# as14120_adc.net
KiCad netlist of a schematic drawn in Altium Designer
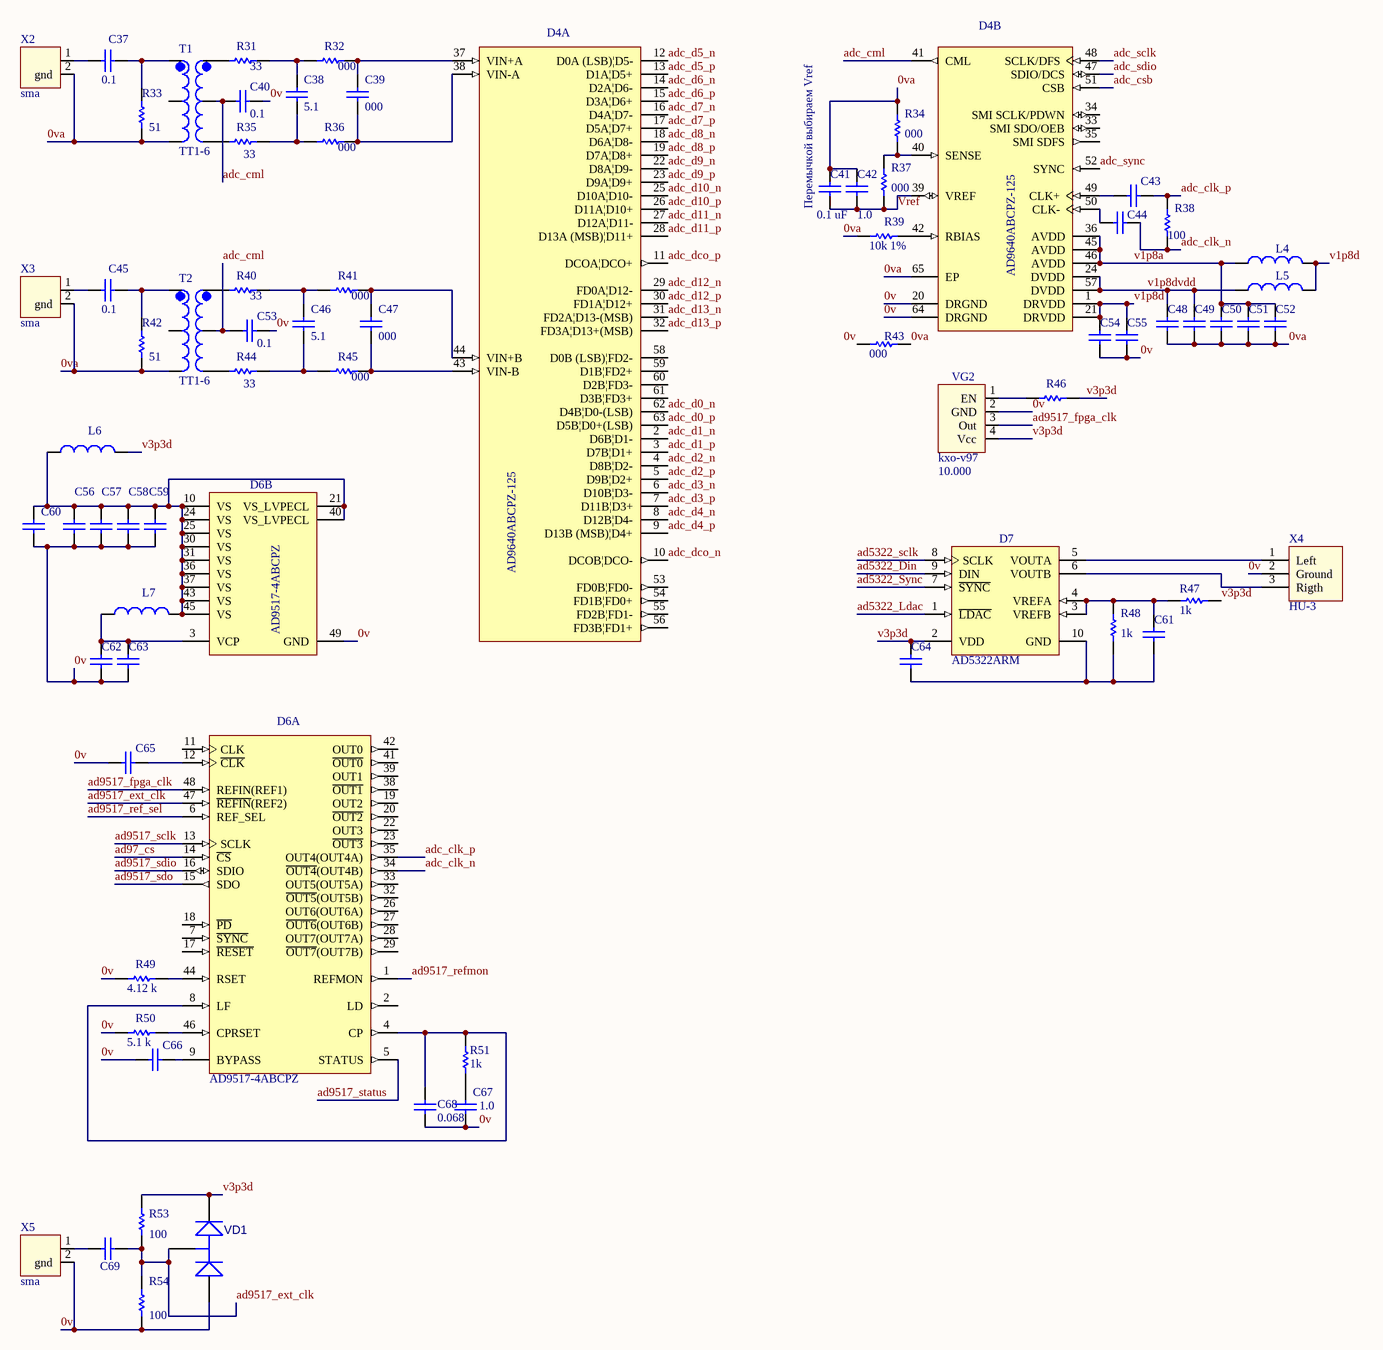
[diagram p0: as14120_adc.SchDoc]

(export (version "E")
  (design (tool "Eeschema 10.0.6"))
  (components
    (comp (ref "C37")
      (value "0.1")
      (footprint "CAPC0402(1005)60_M")
      (description "CAP 1uF 10V ±20% 0402 (1005 Metric) Thickness 0.6mm SMD")
      (fields (field (name "TOLERANCE") "±20%") (field (name "Comment") "CAP 1uF 10V 0402(1005)"))
      (libsource (lib "as14120") (part "CAP_0402"))
    )
    (comp (ref "C38")
      (value "5.1")
      (footprint "CAPC0805(2012)100_N")
      (fields (field (name "Comment") "CAP_0805"))
      (libsource (lib "as14120") (part "CAP_0805"))
    )
    (comp (ref "C39")
      (value "000")
      (footprint "CAPC0805(2012)100_N")
      (fields (field (name "Comment") "CAP_0805"))
      (libsource (lib "as14120") (part "CAP_0805"))
    )
    (comp (ref "C40")
      (value "0.1")
      (footprint "CAPC0402(1005)60_M")
      (description "CAP 1uF 10V ±20% 0402 (1005 Metric) Thickness 0.6mm SMD")
      (fields (field (name "TOLERANCE") "±20%") (field (name "Comment") "CAP 1uF 10V 0402(1005)"))
      (libsource (lib "as14120") (part "CAP_0402"))
    )
    (comp (ref "C41")
      (value "0.1 uF")
      (footprint "CAPC0402(1005)60_M")
      (description "CAP 1uF 10V ±20% 0402 (1005 Metric) Thickness 0.6mm SMD")
      (fields (field (name "TOLERANCE") "±20%") (field (name "Comment") "CAP 1uF 10V 0402(1005)"))
      (libsource (lib "as14120") (part "CAP_0402"))
    )
    (comp (ref "C42")
      (value "1.0")
      (footprint "CAPC0402(1005)60_M")
      (description "CAP 1uF 10V ±20% 0402 (1005 Metric) Thickness 0.6mm SMD")
      (fields (field (name "TOLERANCE") "±20%") (field (name "Comment") "CAP 1uF 10V 0402(1005)"))
      (libsource (lib "as14120") (part "CAP_0402"))
    )
    (comp (ref "C43")
      (value "CAP 1uF 10V 0402(1005)")
      (footprint "CAPC0402(1005)60_M")
      (description "CAP 1uF 10V ±20% 0402 (1005 Metric) Thickness 0.6mm SMD")
      (fields (field (name "TOLERANCE") "±20%"))
      (libsource (lib "as14120") (part "CAP_0402"))
    )
    (comp (ref "C44")
      (value "CAP 1uF 10V 0402(1005)")
      (footprint "CAPC0402(1005)60_M")
      (description "CAP 1uF 10V ±20% 0402 (1005 Metric) Thickness 0.6mm SMD")
      (fields (field (name "TOLERANCE") "±20%"))
      (libsource (lib "as14120") (part "CAP_0402"))
    )
    (comp (ref "C45")
      (value "0.1")
      (footprint "CAPC0402(1005)60_M")
      (description "CAP 1uF 10V ±20% 0402 (1005 Metric) Thickness 0.6mm SMD")
      (fields (field (name "TOLERANCE") "±20%") (field (name "Comment") "CAP 1uF 10V 0402(1005)"))
      (libsource (lib "as14120") (part "CAP_0402"))
    )
    (comp (ref "C46")
      (value "5.1")
      (footprint "CAPC0805(2012)100_N")
      (fields (field (name "Comment") "CAP_0805"))
      (libsource (lib "as14120") (part "CAP_0805"))
    )
    (comp (ref "C47")
      (value "000")
      (footprint "CAPC0805(2012)100_N")
      (fields (field (name "Comment") "CAP_0805"))
      (libsource (lib "as14120") (part "CAP_0805"))
    )
    (comp (ref "C48")
      (value "CAP 1uF 10V 0402(1005)")
      (footprint "CAPC0402(1005)60_M")
      (description "CAP 1uF 10V ±20% 0402 (1005 Metric) Thickness 0.6mm SMD")
      (fields (field (name "TOLERANCE") "±20%"))
      (libsource (lib "as14120") (part "CAP_0402"))
    )
    (comp (ref "C49")
      (value "CAP 1uF 10V 0402(1005)")
      (footprint "CAPC0402(1005)60_M")
      (description "CAP 1uF 10V ±20% 0402 (1005 Metric) Thickness 0.6mm SMD")
      (fields (field (name "TOLERANCE") "±20%"))
      (libsource (lib "as14120") (part "CAP_0402"))
    )
    (comp (ref "C50")
      (value "CAP 1uF 10V 0402(1005)")
      (footprint "CAPC0402(1005)60_M")
      (description "CAP 1uF 10V ±20% 0402 (1005 Metric) Thickness 0.6mm SMD")
      (fields (field (name "TOLERANCE") "±20%"))
      (libsource (lib "as14120") (part "CAP_0402"))
    )
    (comp (ref "C51")
      (value "CAP 1uF 10V 0402(1005)")
      (footprint "CAPC0402(1005)60_M")
      (description "CAP 1uF 10V ±20% 0402 (1005 Metric) Thickness 0.6mm SMD")
      (fields (field (name "TOLERANCE") "±20%"))
      (libsource (lib "as14120") (part "CAP_0402"))
    )
    (comp (ref "C52")
      (value "CAP 1uF 10V 0402(1005)")
      (footprint "CAPC0402(1005)60_M")
      (description "CAP 1uF 10V ±20% 0402 (1005 Metric) Thickness 0.6mm SMD")
      (fields (field (name "TOLERANCE") "±20%"))
      (libsource (lib "as14120") (part "CAP_0402"))
    )
    (comp (ref "C53")
      (value "0.1")
      (footprint "CAPC0402(1005)60_M")
      (description "CAP 1uF 10V ±20% 0402 (1005 Metric) Thickness 0.6mm SMD")
      (fields (field (name "TOLERANCE") "±20%") (field (name "Comment") "CAP 1uF 10V 0402(1005)"))
      (libsource (lib "as14120") (part "CAP_0402"))
    )
    (comp (ref "C54")
      (value "CAP 1uF 10V 0402(1005)")
      (footprint "CAPC0402(1005)60_M")
      (description "CAP 1uF 10V ±20% 0402 (1005 Metric) Thickness 0.6mm SMD")
      (fields (field (name "TOLERANCE") "±20%"))
      (libsource (lib "as14120") (part "CAP_0402"))
    )
    (comp (ref "C55")
      (value "CAP 1uF 10V 0402(1005)")
      (footprint "CAPC0402(1005)60_M")
      (description "CAP 1uF 10V ±20% 0402 (1005 Metric) Thickness 0.6mm SMD")
      (fields (field (name "TOLERANCE") "±20%"))
      (libsource (lib "as14120") (part "CAP_0402"))
    )
    (comp (ref "C56")
      (value "CAP 1uF 10V 0402(1005)")
      (footprint "CAPC0402(1005)60_M")
      (description "CAP 1uF 10V ±20% 0402 (1005 Metric) Thickness 0.6mm SMD")
      (fields (field (name "TOLERANCE") "±20%"))
      (libsource (lib "as14120") (part "CAP_0402"))
    )
    (comp (ref "C57")
      (value "CAP 1uF 10V 0402(1005)")
      (footprint "CAPC0402(1005)60_M")
      (description "CAP 1uF 10V ±20% 0402 (1005 Metric) Thickness 0.6mm SMD")
      (fields (field (name "TOLERANCE") "±20%"))
      (libsource (lib "as14120") (part "CAP_0402"))
    )
    (comp (ref "C58")
      (value "CAP 1uF 10V 0402(1005)")
      (footprint "CAPC0402(1005)60_M")
      (description "CAP 1uF 10V ±20% 0402 (1005 Metric) Thickness 0.6mm SMD")
      (fields (field (name "TOLERANCE") "±20%"))
      (libsource (lib "as14120") (part "CAP_0402"))
    )
    (comp (ref "C59")
      (value "CAP 1uF 10V 0402(1005)")
      (footprint "CAPC0402(1005)60_M")
      (description "CAP 1uF 10V ±20% 0402 (1005 Metric) Thickness 0.6mm SMD")
      (fields (field (name "TOLERANCE") "±20%"))
      (libsource (lib "as14120") (part "CAP_0402"))
    )
    (comp (ref "C60")
      (value "CAP 1uF 10V 0402(1005)")
      (footprint "CAPC0402(1005)60_M")
      (description "CAP 1uF 10V ±20% 0402 (1005 Metric) Thickness 0.6mm SMD")
      (fields (field (name "TOLERANCE") "±20%"))
      (libsource (lib "as14120") (part "CAP_0402"))
    )
    (comp (ref "C61")
      (value "CAP 1uF 10V 0402(1005)")
      (footprint "CAPC0402(1005)60_M")
      (description "CAP 1uF 10V ±20% 0402 (1005 Metric) Thickness 0.6mm SMD")
      (fields (field (name "TOLERANCE") "±20%"))
      (libsource (lib "as14120") (part "CAP_0402"))
    )
    (comp (ref "C62")
      (value "CAP 1uF 10V 0402(1005)")
      (footprint "CAPC0402(1005)60_M")
      (description "CAP 1uF 10V ±20% 0402 (1005 Metric) Thickness 0.6mm SMD")
      (fields (field (name "TOLERANCE") "±20%"))
      (libsource (lib "as14120") (part "CAP_0402"))
    )
    (comp (ref "C63")
      (value "CAP 1uF 10V 0402(1005)")
      (footprint "CAPC0402(1005)60_M")
      (description "CAP 1uF 10V ±20% 0402 (1005 Metric) Thickness 0.6mm SMD")
      (fields (field (name "TOLERANCE") "±20%"))
      (libsource (lib "as14120") (part "CAP_0402"))
    )
    (comp (ref "C64")
      (value "CAP 1uF 10V 0402(1005)")
      (footprint "CAPC0402(1005)60_M")
      (description "CAP 1uF 10V ±20% 0402 (1005 Metric) Thickness 0.6mm SMD")
      (fields (field (name "TOLERANCE") "±20%"))
      (libsource (lib "as14120") (part "CAP_0402"))
    )
    (comp (ref "C65")
      (value "CAP 1uF 10V 0402(1005)")
      (footprint "CAPC0402(1005)60_M")
      (description "CAP 1uF 10V ±20% 0402 (1005 Metric) Thickness 0.6mm SMD")
      (fields (field (name "TOLERANCE") "±20%"))
      (libsource (lib "as14120") (part "CAP_0402"))
    )
    (comp (ref "C66")
      (value "CAP 1uF 10V 0402(1005)")
      (footprint "CAPC0402(1005)60_M")
      (description "CAP 1uF 10V ±20% 0402 (1005 Metric) Thickness 0.6mm SMD")
      (fields (field (name "TOLERANCE") "±20%"))
      (libsource (lib "as14120") (part "CAP_0402"))
    )
    (comp (ref "C67")
      (value "1.0")
      (footprint "CAPC0805(2012)100_N")
      (fields (field (name "Comment") "CAP_0805"))
      (libsource (lib "as14120") (part "CAP_0805"))
    )
    (comp (ref "C68")
      (value "0.068")
      (footprint "CAPC0805(2012)100_N")
      (fields (field (name "Comment") "CAP_0805"))
      (libsource (lib "as14120") (part "CAP_0805"))
    )
    (comp (ref "C69")
      (value "CAP 1uF 10V 0402(1005)")
      (footprint "CAPC0402(1005)60_M")
      (description "CAP 1uF 10V ±20% 0402 (1005 Metric) Thickness 0.6mm SMD")
      (fields (field (name "TOLERANCE") "±20%"))
      (libsource (lib "as14120") (part "CAP_0402"))
    )
    (comp (ref "D4")
      (value "AD9640ABCPZ-125")
      (footprint "CP-64-6_N")
      (fields (field (name "PART NUMBER") "AD9640-125") (field (name "MANUFACTURER") "Analog Devices"))
      (libsource (lib "Analog Devices Data Converters Analog-to-Digital Converters") (part "AD9640ABCPZ-125"))
    )
    (comp (ref "D6")
      (value "AD9517-4ABCPZ")
      (footprint "ADI-CP-48-8_N")
      (libsource (lib "Analog Devices RF IF Timing ICs and Clocks") (part "AD9517-4ABCPZ"))
    )
    (comp (ref "D7")
      (value "AD5322ARM")
      (footprint "RM-10_L")
      (fields (field (name "ADI PART NUMBER") "AD5322") (field (name "MANUFACTURER") "Analog Devices"))
      (libsource (lib "Analog Devices Data Converters Digital-to-Analog Converters") (part "AD5322ARM"))
    )
    (comp (ref "L4")
      (value "BLM21PG300SN1D")
      (footprint "CAPC0805(2012)100_N")
      (libsource (lib "as14120") (part "Ferrite_beat"))
    )
    (comp (ref "L5")
      (value "BLM21PG300SN1D")
      (footprint "CAPC0805(2012)100_N")
      (libsource (lib "as14120") (part "Ferrite_beat"))
    )
    (comp (ref "L6")
      (value "BLM21PG300SN1D")
      (footprint "CAPC0805(2012)100_N")
      (libsource (lib "as14120") (part "Ferrite_beat"))
    )
    (comp (ref "L7")
      (value "BLM21PG300SN1D")
      (footprint "CAPC0805(2012)100_N")
      (libsource (lib "as14120") (part "Ferrite_beat"))
    )
    (comp (ref "R31")
      (value "33")
      (footprint "RESC0805(2012)_L")
      (description "1K 0.125W 1% 0805 (2012 Metric)  SMD")
      (fields (field (name "TOLERANCE") "1 %") (field (name "POWER") "0.125 W"))
      (libsource (lib "as14120") (part "RES_0805"))
    )
    (comp (ref "R32")
      (value "000")
      (footprint "RESC0805(2012)_L")
      (description "1K 0.125W 1% 0805 (2012 Metric)  SMD")
      (fields (field (name "TOLERANCE") "1 %") (field (name "POWER") "0.125 W"))
      (libsource (lib "as14120") (part "RES_0805"))
    )
    (comp (ref "R33")
      (value "51")
      (footprint "RESC0805(2012)_L")
      (description "1K 0.125W 1% 0805 (2012 Metric)  SMD")
      (fields (field (name "TOLERANCE") "1 %") (field (name "POWER") "0.125 W"))
      (libsource (lib "as14120") (part "RES_0805"))
    )
    (comp (ref "R34")
      (value "000")
      (footprint "RESC0603(1608)_L")
      (description "1K 0.1W 5% 0603 (1608 Metric)  SMD")
      (fields (field (name "TOLERANCE") "5 %") (field (name "POWER") "0.1 W"))
      (libsource (lib "as14120") (part "RES_0603"))
    )
    (comp (ref "R35")
      (value "33")
      (footprint "RESC0805(2012)_L")
      (description "1K 0.125W 1% 0805 (2012 Metric)  SMD")
      (fields (field (name "TOLERANCE") "1 %") (field (name "POWER") "0.125 W"))
      (libsource (lib "as14120") (part "RES_0805"))
    )
    (comp (ref "R36")
      (value "000")
      (footprint "RESC0805(2012)_L")
      (description "1K 0.125W 1% 0805 (2012 Metric)  SMD")
      (fields (field (name "TOLERANCE") "1 %") (field (name "POWER") "0.125 W"))
      (libsource (lib "as14120") (part "RES_0805"))
    )
    (comp (ref "R37")
      (value "000")
      (footprint "RESC0603(1608)_L")
      (description "1K 0.1W 5% 0603 (1608 Metric)  SMD")
      (fields (field (name "TOLERANCE") "5 %") (field (name "POWER") "0.1 W"))
      (libsource (lib "as14120") (part "RES_0603"))
    )
    (comp (ref "R38")
      (value "100")
      (footprint "RESC0805(2012)_L")
      (description "1K 0.125W 1% 0805 (2012 Metric)  SMD")
      (fields (field (name "TOLERANCE") "1 %") (field (name "POWER") "0.125 W"))
      (libsource (lib "as14120") (part "RES_0805"))
    )
    (comp (ref "R39")
      (value "10k 1%")
      (footprint "RESC0805(2012)_L")
      (description "1K 0.125W 1% 0805 (2012 Metric)  SMD")
      (fields (field (name "TOLERANCE") "1 %") (field (name "POWER") "0.125 W"))
      (libsource (lib "as14120") (part "RES_0805"))
    )
    (comp (ref "R40")
      (value "33")
      (footprint "RESC0805(2012)_L")
      (description "1K 0.125W 1% 0805 (2012 Metric)  SMD")
      (fields (field (name "TOLERANCE") "1 %") (field (name "POWER") "0.125 W"))
      (libsource (lib "as14120") (part "RES_0805"))
    )
    (comp (ref "R41")
      (value "000")
      (footprint "RESC0805(2012)_L")
      (description "1K 0.125W 1% 0805 (2012 Metric)  SMD")
      (fields (field (name "TOLERANCE") "1 %") (field (name "POWER") "0.125 W"))
      (libsource (lib "as14120") (part "RES_0805"))
    )
    (comp (ref "R42")
      (value "51")
      (footprint "RESC0805(2012)_L")
      (description "1K 0.125W 1% 0805 (2012 Metric)  SMD")
      (fields (field (name "TOLERANCE") "1 %") (field (name "POWER") "0.125 W"))
      (libsource (lib "as14120") (part "RES_0805"))
    )
    (comp (ref "R43")
      (value "000")
      (footprint "RESC0603(1608)_L")
      (description "1K 0.1W 5% 0603 (1608 Metric)  SMD")
      (fields (field (name "TOLERANCE") "5 %") (field (name "POWER") "0.1 W"))
      (libsource (lib "as14120") (part "RES_0603"))
    )
    (comp (ref "R44")
      (value "33")
      (footprint "RESC0805(2012)_L")
      (description "1K 0.125W 1% 0805 (2012 Metric)  SMD")
      (fields (field (name "TOLERANCE") "1 %") (field (name "POWER") "0.125 W"))
      (libsource (lib "as14120") (part "RES_0805"))
    )
    (comp (ref "R45")
      (value "000")
      (footprint "RESC0805(2012)_L")
      (description "1K 0.125W 1% 0805 (2012 Metric)  SMD")
      (fields (field (name "TOLERANCE") "1 %") (field (name "POWER") "0.125 W"))
      (libsource (lib "as14120") (part "RES_0805"))
    )
    (comp (ref "R46")
      (value "1K 5% 0603(1608)")
      (footprint "RESC0603(1608)_L")
      (description "1K 0.1W 5% 0603 (1608 Metric)  SMD")
      (fields (field (name "TOLERANCE") "5 %") (field (name "POWER") "0.1 W"))
      (libsource (lib "as14120") (part "RES_0603"))
    )
    (comp (ref "R47")
      (value "1k")
      (footprint "RESC0603(1608)_L")
      (description "1K 0.1W 5% 0603 (1608 Metric)  SMD")
      (fields (field (name "TOLERANCE") "5 %") (field (name "POWER") "0.1 W"))
      (libsource (lib "as14120") (part "RES_0603"))
    )
    (comp (ref "R48")
      (value "1k")
      (footprint "RESC0603(1608)_L")
      (description "1K 0.1W 5% 0603 (1608 Metric)  SMD")
      (fields (field (name "TOLERANCE") "5 %") (field (name "POWER") "0.1 W"))
      (libsource (lib "as14120") (part "RES_0603"))
    )
    (comp (ref "R49")
      (value "4.12 k")
      (footprint "RESC0805(2012)_L")
      (description "1K 0.125W 1% 0805 (2012 Metric)  SMD")
      (fields (field (name "TOLERANCE") "1 %") (field (name "POWER") "0.125 W"))
      (libsource (lib "as14120") (part "RES_0805"))
    )
    (comp (ref "R50")
      (value "5.1 k")
      (footprint "RESC0805(2012)_L")
      (description "1K 0.125W 1% 0805 (2012 Metric)  SMD")
      (fields (field (name "TOLERANCE") "1 %") (field (name "POWER") "0.125 W"))
      (libsource (lib "as14120") (part "RES_0805"))
    )
    (comp (ref "R51")
      (value "1k")
      (footprint "RESC0805(2012)_L")
      (description "1K 0.125W 1% 0805 (2012 Metric)  SMD")
      (fields (field (name "TOLERANCE") "1 %") (field (name "POWER") "0.125 W"))
      (libsource (lib "as14120") (part "RES_0805"))
    )
    (comp (ref "R53")
      (value "100")
      (footprint "RESC0805(2012)_L")
      (description "1K 0.125W 1% 0805 (2012 Metric)  SMD")
      (fields (field (name "TOLERANCE") "1 %") (field (name "POWER") "0.125 W"))
      (libsource (lib "as14120") (part "RES_0805"))
    )
    (comp (ref "R54")
      (value "100")
      (footprint "RESC0805(2012)_L")
      (description "1K 0.125W 1% 0805 (2012 Metric)  SMD")
      (fields (field (name "TOLERANCE") "1 %") (field (name "POWER") "0.125 W"))
      (libsource (lib "as14120") (part "RES_0805"))
    )
    (comp (ref "T1") (value "TT1-6") (footprint "TT!-6-KK81") (libsource (lib "as14120") (part "TT1-6-KK81")))
    (comp (ref "T2") (value "TT1-6") (footprint "TT!-6-KK81") (libsource (lib "as14120") (part "TT1-6-KK81")))
    (comp (ref "VD1")
      (value "BAV99")
      (footprint "SO-G3/X.9")
      (description "SOT23 Silicon Planar High-Speed Switching Series Diode Pair")
      (libsource (lib "alexsb") (part "BAV99"))
    )
    (comp (ref "VG2")
      (value "kxo-v97")
      (footprint "kxo-v97")
      (fields (field (name "ALTIUM_VALUE") "10.000"))
      (libsource (lib "as14120") (part "kxo-v97"))
    )
    (comp (ref "X2") (value "sma") (footprint "sma") (libsource (lib "as14120") (part "sma")))
    (comp (ref "X3") (value "sma") (footprint "sma") (libsource (lib "as14120") (part "sma")))
    (comp (ref "X4") (value "HU-3") (footprint "HU-3") (libsource (lib "as14120") (part "HU-3")))
    (comp (ref "X5") (value "sma") (footprint "sma") (libsource (lib "as14120") (part "sma")))
  )
  (nets
    (net (code "1") (name "/0v") (class "Default")
      (node (ref "C40") (pin "2") (pinfunction "2_2") (pintype "passive"))
      (node (ref "C53") (pin "2") (pinfunction "2_2") (pintype "passive"))
      (node (ref "C54") (pin "1") (pinfunction "1_1") (pintype "passive"))
      (node (ref "C55") (pin "1") (pinfunction "1_1") (pintype "passive"))
      (node (ref "C56") (pin "1") (pinfunction "1_1") (pintype "passive"))
      (node (ref "C57") (pin "1") (pinfunction "1_1") (pintype "passive"))
      (node (ref "C58") (pin "1") (pinfunction "1_1") (pintype "passive"))
      (node (ref "C59") (pin "1") (pinfunction "1_1") (pintype "passive"))
      (node (ref "C60") (pin "1") (pinfunction "1_1") (pintype "passive"))
      (node (ref "C62") (pin "1") (pinfunction "1_1") (pintype "passive"))
      (node (ref "C63") (pin "1") (pinfunction "1_1") (pintype "passive"))
      (node (ref "C65") (pin "1") (pinfunction "1_1") (pintype "passive"))
      (node (ref "C66") (pin "1") (pinfunction "1_1") (pintype "passive"))
      (node (ref "C67") (pin "1") (pinfunction "1_1") (pintype "passive"))
      (node (ref "C68") (pin "1") (pinfunction "1_1") (pintype "passive"))
      (node (ref "D4") (pin "20") (pinfunction "DRGND_20") (pintype "power_in"))
      (node (ref "D4") (pin "64") (pinfunction "DRGND_64") (pintype "power_in"))
      (node (ref "D6") (pin "49") (pinfunction "GND_49") (pintype "power_in"))
      (node (ref "R49") (pin "2") (pinfunction "2_2") (pintype "passive"))
      (node (ref "R50") (pin "2") (pinfunction "2_2") (pintype "passive"))
      (node (ref "R54") (pin "1") (pinfunction "1_1") (pintype "passive"))
      (node (ref "VD1") (pin "3") (pinfunction "A_3") (pintype "passive"))
      (node (ref "VG2") (pin "2") (pinfunction "GND_2") (pintype "passive"))
      (node (ref "X4") (pin "2") (pinfunction "Ground_2") (pintype "passive"))
      (node (ref "X5") (pin "2") (pinfunction "gnd_2") (pintype "passive"))
    )
    (net (code "2") (name "/0va") (class "Default")
      (node (ref "C41") (pin "2") (pinfunction "2_2") (pintype "passive"))
      (node (ref "C42") (pin "2") (pinfunction "2_2") (pintype "passive"))
      (node (ref "C48") (pin "1") (pinfunction "1_1") (pintype "passive"))
      (node (ref "C49") (pin "1") (pinfunction "1_1") (pintype "passive"))
      (node (ref "C50") (pin "1") (pinfunction "1_1") (pintype "passive"))
      (node (ref "C51") (pin "1") (pinfunction "1_1") (pintype "passive"))
      (node (ref "C52") (pin "1") (pinfunction "1_1") (pintype "passive"))
      (node (ref "D4") (pin "65") (pinfunction "EP_65") (pintype "power_in"))
      (node (ref "R33") (pin "1") (pinfunction "1_1") (pintype "passive"))
      (node (ref "R34") (pin "1") (pinfunction "1_1") (pintype "passive"))
      (node (ref "R39") (pin "2") (pinfunction "2_2") (pintype "passive"))
      (node (ref "R42") (pin "1") (pinfunction "1_1") (pintype "passive"))
      (node (ref "R43") (pin "2") (pinfunction "2_2") (pintype "passive"))
      (node (ref "T1") (pin "6") (pinfunction "6_6") (pintype "passive"))
      (node (ref "T2") (pin "6") (pinfunction "6_6") (pintype "passive"))
      (node (ref "X2") (pin "2") (pinfunction "gnd_2") (pintype "passive"))
      (node (ref "X3") (pin "2") (pinfunction "gnd_2") (pintype "passive"))
    )
    (net (code "3") (name "/Vref") (class "Default")
      (node (ref "C41") (pin "1") (pinfunction "1_1") (pintype "passive"))
      (node (ref "C42") (pin "1") (pinfunction "1_1") (pintype "passive"))
      (node (ref "D4") (pin "39") (pinfunction "VREF_39") (pintype "bidirectional"))
      (node (ref "R37") (pin "2") (pinfunction "2_2") (pintype "passive"))
    )
    (net (code "4") (name "/ad97_cs") (class "Default")
      (node (ref "D6") (pin "14") (pinfunction "~{CS}_14") (pintype "input"))
    )
    (net (code "5") (name "/ad5322_Din") (class "Default")
      (node (ref "D7") (pin "9") (pinfunction "DIN_9") (pintype "input"))
    )
    (net (code "6") (name "/ad5322_Ldac") (class "Default")
      (node (ref "D7") (pin "1") (pinfunction "~{LDAC}_1") (pintype "input"))
    )
    (net (code "7") (name "/ad5322_Sync") (class "Default")
      (node (ref "D7") (pin "7") (pinfunction "~{SYNC}_7") (pintype "input"))
    )
    (net (code "8") (name "/ad5322_sclk") (class "Default")
      (node (ref "D7") (pin "8") (pinfunction "SCLK_8") (pintype "input"))
    )
    (net (code "9") (name "/ad9517_ext_clk") (class "Default")
      (node (ref "C69") (pin "2") (pinfunction "2_2") (pintype "passive"))
      (node (ref "D6") (pin "47") (pinfunction "~{REFIN}(REF2)_47") (pintype "input"))
      (node (ref "R53") (pin "1") (pinfunction "1_1") (pintype "passive"))
      (node (ref "R54") (pin "2") (pinfunction "2_2") (pintype "passive"))
      (node (ref "VD1") (pin "1") (pinfunction "C_1") (pintype "passive"))
    )
    (net (code "10") (name "/ad9517_fpga_clk") (class "Default")
      (node (ref "D6") (pin "48") (pinfunction "REFIN(REF1)_48") (pintype "input"))
      (node (ref "VG2") (pin "3") (pinfunction "Out_3") (pintype "passive"))
    )
    (net (code "11") (name "/ad9517_ref_sel") (class "Default")
      (node (ref "D6") (pin "6") (pinfunction "REF_SEL_6") (pintype "input"))
    )
    (net (code "12") (name "/ad9517_refmon") (class "Default")
      (node (ref "D6") (pin "1") (pinfunction "REFMON_1") (pintype "output"))
    )
    (net (code "13") (name "/ad9517_sclk") (class "Default")
      (node (ref "D6") (pin "13") (pinfunction "SCLK_13") (pintype "input"))
    )
    (net (code "14") (name "/ad9517_sdio") (class "Default")
      (node (ref "D6") (pin "16") (pinfunction "SDIO_16") (pintype "bidirectional"))
    )
    (net (code "15") (name "/ad9517_sdo") (class "Default")
      (node (ref "D6") (pin "15") (pinfunction "SDO_15") (pintype "output"))
    )
    (net (code "16") (name "/ad9517_status") (class "Default")
      (node (ref "D6") (pin "5") (pinfunction "STATUS_5") (pintype "output"))
    )
    (net (code "17") (name "/adc_clk_n") (class "Default")
      (node (ref "C44") (pin "1") (pinfunction "1_1") (pintype "passive"))
      (node (ref "D6") (pin "34") (pinfunction "~{OUT4}(OUT4B)_34") (pintype "output"))
      (node (ref "R38") (pin "1") (pinfunction "1_1") (pintype "passive"))
    )
    (net (code "18") (name "/adc_clk_p") (class "Default")
      (node (ref "C43") (pin "1") (pinfunction "1_1") (pintype "passive"))
      (node (ref "D6") (pin "35") (pinfunction "OUT4(OUT4A)_35") (pintype "output"))
      (node (ref "R38") (pin "2") (pinfunction "2_2") (pintype "passive"))
    )
    (net (code "19") (name "/adc_cml") (class "Default")
      (node (ref "C40") (pin "1") (pinfunction "1_1") (pintype "passive"))
      (node (ref "C53") (pin "1") (pinfunction "1_1") (pintype "passive"))
      (node (ref "D4") (pin "41") (pinfunction "CML_41") (pintype "output"))
      (node (ref "T1") (pin "2") (pinfunction "2_2") (pintype "passive"))
      (node (ref "T2") (pin "2") (pinfunction "2_2") (pintype "passive"))
    )
    (net (code "20") (name "/adc_csb") (class "Default")
      (node (ref "D4") (pin "51") (pinfunction "CSB_51") (pintype "input"))
    )
    (net (code "21") (name "/adc_d0_n") (class "Default")
      (node (ref "D4") (pin "62") (pinfunction "D4B¦D0-(LSB)_62") (pintype "tri_state"))
    )
    (net (code "22") (name "/adc_d0_p") (class "Default")
      (node (ref "D4") (pin "63") (pinfunction "D5B¦D0+(LSB)_63") (pintype "tri_state"))
    )
    (net (code "23") (name "/adc_d1_n") (class "Default")
      (node (ref "D4") (pin "2") (pinfunction "D6B¦D1-_2") (pintype "tri_state"))
    )
    (net (code "24") (name "/adc_d1_p") (class "Default")
      (node (ref "D4") (pin "3") (pinfunction "D7B¦D1+_3") (pintype "tri_state"))
    )
    (net (code "25") (name "/adc_d2_n") (class "Default")
      (node (ref "D4") (pin "4") (pinfunction "D8B¦D2-_4") (pintype "tri_state"))
    )
    (net (code "26") (name "/adc_d2_p") (class "Default")
      (node (ref "D4") (pin "5") (pinfunction "D9B¦D2+_5") (pintype "tri_state"))
    )
    (net (code "27") (name "/adc_d3_n") (class "Default")
      (node (ref "D4") (pin "6") (pinfunction "D10B¦D3-_6") (pintype "tri_state"))
    )
    (net (code "28") (name "/adc_d3_p") (class "Default")
      (node (ref "D4") (pin "7") (pinfunction "D11B¦D3+_7") (pintype "tri_state"))
    )
    (net (code "29") (name "/adc_d4_n") (class "Default")
      (node (ref "D4") (pin "8") (pinfunction "D12B¦D4-_8") (pintype "tri_state"))
    )
    (net (code "30") (name "/adc_d4_p") (class "Default")
      (node (ref "D4") (pin "9") (pinfunction "D13B_(MSB)¦D4+_9") (pintype "tri_state"))
    )
    (net (code "31") (name "/adc_d5_n") (class "Default")
      (node (ref "D4") (pin "12") (pinfunction "D0A_(LSB)¦D5-_12") (pintype "tri_state"))
    )
    (net (code "32") (name "/adc_d5_p") (class "Default")
      (node (ref "D4") (pin "13") (pinfunction "D1A¦D5+_13") (pintype "tri_state"))
    )
    (net (code "33") (name "/adc_d6_n") (class "Default")
      (node (ref "D4") (pin "14") (pinfunction "D2A¦D6-_14") (pintype "tri_state"))
    )
    (net (code "34") (name "/adc_d6_p") (class "Default")
      (node (ref "D4") (pin "15") (pinfunction "D3A¦D6+_15") (pintype "tri_state"))
    )
    (net (code "35") (name "/adc_d7_n") (class "Default")
      (node (ref "D4") (pin "16") (pinfunction "D4A¦D7-_16") (pintype "tri_state"))
    )
    (net (code "36") (name "/adc_d7_p") (class "Default")
      (node (ref "D4") (pin "17") (pinfunction "D5A¦D7+_17") (pintype "tri_state"))
    )
    (net (code "37") (name "/adc_d8_n") (class "Default")
      (node (ref "D4") (pin "18") (pinfunction "D6A¦D8-_18") (pintype "tri_state"))
    )
    (net (code "38") (name "/adc_d8_p") (class "Default")
      (node (ref "D4") (pin "19") (pinfunction "D7A¦D8+_19") (pintype "tri_state"))
    )
    (net (code "39") (name "/adc_d9_n") (class "Default")
      (node (ref "D4") (pin "22") (pinfunction "D8A¦D9-_22") (pintype "tri_state"))
    )
    (net (code "40") (name "/adc_d9_p") (class "Default")
      (node (ref "D4") (pin "23") (pinfunction "D9A¦D9+_23") (pintype "tri_state"))
    )
    (net (code "41") (name "/adc_d10_n") (class "Default")
      (node (ref "D4") (pin "25") (pinfunction "D10A¦D10-_25") (pintype "tri_state"))
    )
    (net (code "42") (name "/adc_d10_p") (class "Default")
      (node (ref "D4") (pin "26") (pinfunction "D11A¦D10+_26") (pintype "tri_state"))
    )
    (net (code "43") (name "/adc_d11_n") (class "Default")
      (node (ref "D4") (pin "27") (pinfunction "D12A¦D11-_27") (pintype "tri_state"))
    )
    (net (code "44") (name "/adc_d11_p") (class "Default")
      (node (ref "D4") (pin "28") (pinfunction "D13A_(MSB)¦D11+_28") (pintype "tri_state"))
    )
    (net (code "45") (name "/adc_d12_n") (class "Default")
      (node (ref "D4") (pin "29") (pinfunction "FD0A¦D12-_29") (pintype "tri_state"))
    )
    (net (code "46") (name "/adc_d12_p") (class "Default")
      (node (ref "D4") (pin "30") (pinfunction "FD1A¦D12+_30") (pintype "tri_state"))
    )
    (net (code "47") (name "/adc_d13_n") (class "Default")
      (node (ref "D4") (pin "31") (pinfunction "FD2A¦D13-(MSB)_31") (pintype "tri_state"))
    )
    (net (code "48") (name "/adc_d13_p") (class "Default")
      (node (ref "D4") (pin "32") (pinfunction "FD3A¦D13+(MSB)_32") (pintype "tri_state"))
    )
    (net (code "49") (name "/adc_dco_n") (class "Default")
      (node (ref "D4") (pin "10") (pinfunction "DCOB¦DCO-_10") (pintype "output"))
    )
    (net (code "50") (name "/adc_dco_p") (class "Default")
      (node (ref "D4") (pin "11") (pinfunction "DCOA¦DCO+_11") (pintype "output"))
    )
    (net (code "51") (name "/adc_sclk") (class "Default")
      (node (ref "D4") (pin "48") (pinfunction "SCLK/DFS_48") (pintype "input"))
    )
    (net (code "52") (name "/adc_sdio") (class "Default")
      (node (ref "D4") (pin "47") (pinfunction "SDIO/DCS_47") (pintype "bidirectional"))
    )
    (net (code "53") (name "/adc_sync") (class "Default")
      (node (ref "D4") (pin "52") (pinfunction "SYNC_52") (pintype "input"))
    )
    (net (code "54") (name "/v1p8a") (class "Default")
      (node (ref "C50") (pin "2") (pinfunction "2_2") (pintype "passive"))
      (node (ref "C51") (pin "2") (pinfunction "2_2") (pintype "passive"))
      (node (ref "C52") (pin "2") (pinfunction "2_2") (pintype "passive"))
      (node (ref "D4") (pin "36") (pinfunction "AVDD_36") (pintype "power_in"))
      (node (ref "D4") (pin "45") (pinfunction "AVDD_45") (pintype "power_in"))
      (node (ref "D4") (pin "46") (pinfunction "AVDD_46") (pintype "power_in"))
      (node (ref "L4") (pin "1") (pinfunction "1_1") (pintype "passive"))
    )
    (net (code "55") (name "/v1p8d") (class "Default")
      (node (ref "C54") (pin "2") (pinfunction "2_2") (pintype "passive"))
      (node (ref "C55") (pin "2") (pinfunction "2_2") (pintype "passive"))
      (node (ref "D4") (pin "1") (pinfunction "DRVDD_1") (pintype "power_in"))
      (node (ref "D4") (pin "21") (pinfunction "DRVDD_21") (pintype "power_in"))
      (node (ref "L4") (pin "2") (pinfunction "2_2") (pintype "passive"))
      (node (ref "L5") (pin "2") (pinfunction "2_2") (pintype "passive"))
    )
    (net (code "56") (name "/v1p8dvdd") (class "Default")
      (node (ref "C48") (pin "2") (pinfunction "2_2") (pintype "passive"))
      (node (ref "C49") (pin "2") (pinfunction "2_2") (pintype "passive"))
      (node (ref "D4") (pin "24") (pinfunction "DVDD_24") (pintype "power_in"))
      (node (ref "D4") (pin "57") (pinfunction "DVDD_57") (pintype "power_in"))
      (node (ref "L5") (pin "1") (pinfunction "1_1") (pintype "passive"))
    )
    (net (code "57") (name "/v3p3d") (class "Default")
      (node (ref "C64") (pin "2") (pinfunction "2_2") (pintype "passive"))
      (node (ref "D7") (pin "2") (pinfunction "VDD_2") (pintype "power_in"))
      (node (ref "L6") (pin "2") (pinfunction "2_2") (pintype "passive"))
      (node (ref "R46") (pin "1") (pinfunction "1_1") (pintype "passive"))
      (node (ref "R47") (pin "2") (pinfunction "2_2") (pintype "passive"))
      (node (ref "R53") (pin "2") (pinfunction "2_2") (pintype "passive"))
      (node (ref "VD1") (pin "2") (pinfunction "K_2") (pintype "passive"))
      (node (ref "VG2") (pin "4") (pinfunction "Vcc_4") (pintype "passive"))
    )
    (net (code "58") (name "Net-(C37-Pad1)") (class "Default")
      (node (ref "C37") (pin "1") (pinfunction "1_1") (pintype "passive"))
      (node (ref "X2") (pin "1") (pintype "passive"))
    )
    (net (code "59") (name "Net-(C37-Pad2)") (class "Default")
      (node (ref "C37") (pin "2") (pinfunction "2_2") (pintype "passive"))
      (node (ref "R33") (pin "2") (pinfunction "2_2") (pintype "passive"))
      (node (ref "T1") (pin "4") (pinfunction "4_4") (pintype "passive"))
    )
    (net (code "60") (name "Net-(C38-Pad1)") (class "Default")
      (node (ref "C38") (pin "1") (pinfunction "1_1") (pintype "passive"))
      (node (ref "R35") (pin "1") (pinfunction "1_1") (pintype "passive"))
      (node (ref "R36") (pin "2") (pinfunction "2_2") (pintype "passive"))
    )
    (net (code "61") (name "Net-(C38-Pad2)") (class "Default")
      (node (ref "C38") (pin "2") (pinfunction "2_2") (pintype "passive"))
      (node (ref "R31") (pin "1") (pinfunction "1_1") (pintype "passive"))
      (node (ref "R32") (pin "2") (pinfunction "2_2") (pintype "passive"))
    )
    (net (code "62") (name "Net-(C45-Pad1)") (class "Default")
      (node (ref "C45") (pin "1") (pinfunction "1_1") (pintype "passive"))
      (node (ref "X3") (pin "1") (pintype "passive"))
    )
    (net (code "63") (name "Net-(C45-Pad2)") (class "Default")
      (node (ref "C45") (pin "2") (pinfunction "2_2") (pintype "passive"))
      (node (ref "R42") (pin "2") (pinfunction "2_2") (pintype "passive"))
      (node (ref "T2") (pin "4") (pinfunction "4_4") (pintype "passive"))
    )
    (net (code "64") (name "Net-(C46-Pad1)") (class "Default")
      (node (ref "C46") (pin "1") (pinfunction "1_1") (pintype "passive"))
      (node (ref "R44") (pin "1") (pinfunction "1_1") (pintype "passive"))
      (node (ref "R45") (pin "2") (pinfunction "2_2") (pintype "passive"))
    )
    (net (code "65") (name "Net-(C46-Pad2)") (class "Default")
      (node (ref "C46") (pin "2") (pinfunction "2_2") (pintype "passive"))
      (node (ref "R40") (pin "1") (pinfunction "1_1") (pintype "passive"))
      (node (ref "R41") (pin "2") (pinfunction "2_2") (pintype "passive"))
    )
    (net (code "66") (name "Net-(C56-Pad2)") (class "Default")
      (node (ref "C56") (pin "2") (pinfunction "2_2") (pintype "passive"))
      (node (ref "C57") (pin "2") (pinfunction "2_2") (pintype "passive"))
      (node (ref "C58") (pin "2") (pinfunction "2_2") (pintype "passive"))
      (node (ref "C59") (pin "2") (pinfunction "2_2") (pintype "passive"))
      (node (ref "C60") (pin "2") (pinfunction "2_2") (pintype "passive"))
      (node (ref "D6") (pin "10") (pinfunction "VS_10") (pintype "power_in"))
      (node (ref "D6") (pin "21") (pinfunction "VS_LVPECL_21") (pintype "power_in"))
      (node (ref "D6") (pin "24") (pinfunction "VS_24") (pintype "power_in"))
      (node (ref "D6") (pin "25") (pinfunction "VS_25") (pintype "power_in"))
      (node (ref "D6") (pin "30") (pinfunction "VS_30") (pintype "power_in"))
      (node (ref "D6") (pin "31") (pinfunction "VS_31") (pintype "power_in"))
      (node (ref "D6") (pin "36") (pinfunction "VS_36") (pintype "power_in"))
      (node (ref "D6") (pin "37") (pinfunction "VS_37") (pintype "power_in"))
      (node (ref "D6") (pin "40") (pinfunction "VS_LVPECL_40") (pintype "power_in"))
      (node (ref "D6") (pin "43") (pinfunction "VS_43") (pintype "power_in"))
      (node (ref "D6") (pin "45") (pinfunction "VS_45") (pintype "power_in"))
      (node (ref "L6") (pin "1") (pinfunction "1_1") (pintype "passive"))
      (node (ref "L7") (pin "2") (pinfunction "2_2") (pintype "passive"))
    )
    (net (code "67") (name "Net-(C67-Pad2)") (class "Default")
      (node (ref "C67") (pin "2") (pinfunction "2_2") (pintype "passive"))
      (node (ref "R51") (pin "2") (pinfunction "2_2") (pintype "passive"))
    )
    (net (code "68") (name "Net-(C69-Pad1)") (class "Default")
      (node (ref "C69") (pin "1") (pinfunction "1_1") (pintype "passive"))
      (node (ref "X5") (pin "1") (pintype "passive"))
    )
    (net (code "69") (name "Net-(D4A-VIN+A)") (class "Default")
      (node (ref "C39") (pin "2") (pinfunction "2_2") (pintype "passive"))
      (node (ref "D4") (pin "37") (pinfunction "VIN+A_37") (pintype "input"))
      (node (ref "R32") (pin "1") (pinfunction "1_1") (pintype "passive"))
    )
    (net (code "70") (name "Net-(D4A-VIN+B)") (class "Default")
      (node (ref "C47") (pin "2") (pinfunction "2_2") (pintype "passive"))
      (node (ref "D4") (pin "44") (pinfunction "VIN+B_44") (pintype "input"))
      (node (ref "R41") (pin "1") (pinfunction "1_1") (pintype "passive"))
    )
    (net (code "71") (name "Net-(D4A-VIN-A)") (class "Default")
      (node (ref "C39") (pin "1") (pinfunction "1_1") (pintype "passive"))
      (node (ref "D4") (pin "38") (pinfunction "VIN-A_38") (pintype "input"))
      (node (ref "R36") (pin "1") (pinfunction "1_1") (pintype "passive"))
    )
    (net (code "72") (name "Net-(D4A-VIN-B)") (class "Default")
      (node (ref "C47") (pin "1") (pinfunction "1_1") (pintype "passive"))
      (node (ref "D4") (pin "43") (pinfunction "VIN-B_43") (pintype "input"))
      (node (ref "R45") (pin "1") (pinfunction "1_1") (pintype "passive"))
    )
    (net (code "73") (name "Net-(D4B-CLK+)") (class "Default")
      (node (ref "C43") (pin "2") (pinfunction "2_2") (pintype "passive"))
      (node (ref "D4") (pin "49") (pinfunction "CLK+_49") (pintype "input"))
    )
    (net (code "74") (name "Net-(D4B-CLK-)") (class "Default")
      (node (ref "C44") (pin "2") (pinfunction "2_2") (pintype "passive"))
      (node (ref "D4") (pin "50") (pinfunction "CLK-_50") (pintype "input"))
    )
    (net (code "75") (name "Net-(D4B-RBIAS)") (class "Default")
      (node (ref "D4") (pin "42") (pinfunction "RBIAS_42") (pintype "input"))
      (node (ref "R39") (pin "1") (pinfunction "1_1") (pintype "passive"))
    )
    (net (code "76") (name "Net-(D4B-SENSE)") (class "Default")
      (node (ref "D4") (pin "40") (pinfunction "SENSE_40") (pintype "input"))
      (node (ref "R34") (pin "2") (pinfunction "2_2") (pintype "passive"))
      (node (ref "R37") (pin "1") (pinfunction "1_1") (pintype "passive"))
    )
    (net (code "77") (name "Net-(D6A-BYPASS)") (class "Default")
      (node (ref "C66") (pin "2") (pinfunction "2_2") (pintype "passive"))
      (node (ref "D6") (pin "9") (pinfunction "BYPASS_9") (pintype "passive"))
    )
    (net (code "78") (name "Net-(D6A-CP)") (class "Default")
      (node (ref "C68") (pin "2") (pinfunction "2_2") (pintype "passive"))
      (node (ref "D6") (pin "4") (pinfunction "CP_4") (pintype "output"))
      (node (ref "D6") (pin "8") (pinfunction "LF_8") (pintype "input"))
      (node (ref "R51") (pin "1") (pinfunction "1_1") (pintype "passive"))
    )
    (net (code "79") (name "Net-(D6A-CPRSET)") (class "Default")
      (node (ref "D6") (pin "46") (pinfunction "CPRSET_46") (pintype "input"))
      (node (ref "R50") (pin "1") (pinfunction "1_1") (pintype "passive"))
    )
    (net (code "80") (name "Net-(D6A-RSET)") (class "Default")
      (node (ref "D6") (pin "44") (pinfunction "RSET_44") (pintype "input"))
      (node (ref "R49") (pin "1") (pinfunction "1_1") (pintype "passive"))
    )
    (net (code "81") (name "Net-(D6A-~{CLK})") (class "Default")
      (node (ref "C65") (pin "2") (pinfunction "2_2") (pintype "passive"))
      (node (ref "D6") (pin "12") (pinfunction "~{CLK}_12") (pintype "input"))
    )
    (net (code "82") (name "Net-(D6B-VCP)") (class "Default")
      (node (ref "C62") (pin "2") (pinfunction "2_2") (pintype "passive"))
      (node (ref "C63") (pin "2") (pinfunction "2_2") (pintype "passive"))
      (node (ref "D6") (pin "3") (pinfunction "VCP_3") (pintype "power_in"))
      (node (ref "L7") (pin "1") (pinfunction "1_1") (pintype "passive"))
    )
    (net (code "83") (name "Net-(D7-GND)") (class "Default")
      (node (ref "C61") (pin "1") (pinfunction "1_1") (pintype "passive"))
      (node (ref "C64") (pin "1") (pinfunction "1_1") (pintype "passive"))
      (node (ref "D7") (pin "10") (pinfunction "GND_10") (pintype "power_in"))
      (node (ref "R48") (pin "2") (pinfunction "2_2") (pintype "passive"))
    )
    (net (code "84") (name "Net-(D7-VOUTA)") (class "Default")
      (node (ref "D7") (pin "5") (pinfunction "VOUTA_5") (pintype "tri_state"))
      (node (ref "X4") (pin "1") (pinfunction "Left_1") (pintype "passive"))
    )
    (net (code "85") (name "Net-(D7-VOUTB)") (class "Default")
      (node (ref "D7") (pin "6") (pinfunction "VOUTB_6") (pintype "tri_state"))
      (node (ref "X4") (pin "3") (pinfunction "Rigth_3") (pintype "passive"))
    )
    (net (code "86") (name "Net-(D7-VREFA)") (class "Default")
      (node (ref "C61") (pin "2") (pinfunction "2_2") (pintype "passive"))
      (node (ref "D7") (pin "3") (pinfunction "VREFB_3") (pintype "input"))
      (node (ref "D7") (pin "4") (pinfunction "VREFA_4") (pintype "input"))
      (node (ref "R47") (pin "1") (pinfunction "1_1") (pintype "passive"))
      (node (ref "R48") (pin "1") (pinfunction "1_1") (pintype "passive"))
    )
    (net (code "87") (name "Net-(R31-Pad2)") (class "Default")
      (node (ref "R31") (pin "2") (pinfunction "2_2") (pintype "passive"))
      (node (ref "T1") (pin "3") (pinfunction "3_3") (pintype "passive"))
    )
    (net (code "88") (name "Net-(R35-Pad2)") (class "Default")
      (node (ref "R35") (pin "2") (pinfunction "2_2") (pintype "passive"))
      (node (ref "T1") (pin "1") (pinfunction "1_1") (pintype "passive"))
    )
    (net (code "89") (name "Net-(R40-Pad2)") (class "Default")
      (node (ref "R40") (pin "2") (pinfunction "2_2") (pintype "passive"))
      (node (ref "T2") (pin "3") (pinfunction "3_3") (pintype "passive"))
    )
    (net (code "90") (name "Net-(R44-Pad2)") (class "Default")
      (node (ref "R44") (pin "2") (pinfunction "2_2") (pintype "passive"))
      (node (ref "T2") (pin "1") (pinfunction "1_1") (pintype "passive"))
    )
    (net (code "91") (name "Net-(VG2-EN)") (class "Default")
      (node (ref "R46") (pin "2") (pinfunction "2_2") (pintype "passive"))
      (node (ref "VG2") (pin "1") (pinfunction "EN_1") (pintype "passive"))
    )
    (net (code "92") (name "unconnected-(D4A-D0B_(LSB)¦FD2--Pad58)") (class "Default")
      (node (ref "D4") (pin "58") (pinfunction "D0B_(LSB)¦FD2-_58") (pintype "tri_state"))
    )
    (net (code "93") (name "unconnected-(D4A-D1B¦FD2+-Pad59)") (class "Default")
      (node (ref "D4") (pin "59") (pinfunction "D1B¦FD2+_59") (pintype "tri_state"))
    )
    (net (code "94") (name "unconnected-(D4A-D2B¦FD3--Pad60)") (class "Default")
      (node (ref "D4") (pin "60") (pinfunction "D2B¦FD3-_60") (pintype "tri_state"))
    )
    (net (code "95") (name "unconnected-(D4A-D3B¦FD3+-Pad61)") (class "Default")
      (node (ref "D4") (pin "61") (pinfunction "D3B¦FD3+_61") (pintype "tri_state"))
    )
    (net (code "96") (name "unconnected-(D4A-FD0B¦FD0--Pad53)") (class "Default")
      (node (ref "D4") (pin "53") (pinfunction "FD0B¦FD0-_53") (pintype "output"))
    )
    (net (code "97") (name "unconnected-(D4A-FD1B¦FD0+-Pad54)") (class "Default")
      (node (ref "D4") (pin "54") (pinfunction "FD1B¦FD0+_54") (pintype "output"))
    )
    (net (code "98") (name "unconnected-(D4A-FD2B¦FD1--Pad55)") (class "Default")
      (node (ref "D4") (pin "55") (pinfunction "FD2B¦FD1-_55") (pintype "output"))
    )
    (net (code "99") (name "unconnected-(D4A-FD3B¦FD1+-Pad56)") (class "Default")
      (node (ref "D4") (pin "56") (pinfunction "FD3B¦FD1+_56") (pintype "output"))
    )
    (net (code "100") (name "unconnected-(D4B-SMI_SCLK{slash}PDWN-Pad34)") (class "Default")
      (node (ref "D4") (pin "34") (pinfunction "SMI_SCLK/PDWN_34") (pintype "bidirectional"))
    )
    (net (code "101") (name "unconnected-(D4B-SMI_SDFS-Pad35)") (class "Default")
      (node (ref "D4") (pin "35") (pinfunction "SMI_SDFS_35") (pintype "output"))
    )
    (net (code "102") (name "unconnected-(D4B-SMI_SDO{slash}OEB-Pad33)") (class "Default")
      (node (ref "D4") (pin "33") (pinfunction "SMI_SDO/OEB_33") (pintype "bidirectional"))
    )
    (net (code "103") (name "unconnected-(D6A-CLK-Pad11)") (class "Default")
      (node (ref "D6") (pin "11") (pinfunction "CLK_11") (pintype "input"))
    )
    (net (code "104") (name "unconnected-(D6A-LD-Pad2)") (class "Default")
      (node (ref "D6") (pin "2") (pinfunction "LD_2") (pintype "output"))
    )
    (net (code "105") (name "unconnected-(D6A-OUT0-Pad42)") (class "Default")
      (node (ref "D6") (pin "42") (pinfunction "OUT0_42") (pintype "output"))
    )
    (net (code "106") (name "unconnected-(D6A-OUT1-Pad39)") (class "Default")
      (node (ref "D6") (pin "39") (pinfunction "OUT1_39") (pintype "output"))
    )
    (net (code "107") (name "unconnected-(D6A-OUT2-Pad19)") (class "Default")
      (node (ref "D6") (pin "19") (pinfunction "OUT2_19") (pintype "output"))
    )
    (net (code "108") (name "unconnected-(D6A-OUT3-Pad22)") (class "Default")
      (node (ref "D6") (pin "22") (pinfunction "OUT3_22") (pintype "output"))
    )
    (net (code "109") (name "unconnected-(D6A-OUT5(OUT5A)-Pad33)") (class "Default")
      (node (ref "D6") (pin "33") (pinfunction "OUT5(OUT5A)_33") (pintype "output"))
    )
    (net (code "110") (name "unconnected-(D6A-OUT6(OUT6A)-Pad26)") (class "Default")
      (node (ref "D6") (pin "26") (pinfunction "OUT6(OUT6A)_26") (pintype "output"))
    )
    (net (code "111") (name "unconnected-(D6A-OUT7(OUT7A)-Pad28)") (class "Default")
      (node (ref "D6") (pin "28") (pinfunction "OUT7(OUT7A)_28") (pintype "output"))
    )
    (net (code "112") (name "unconnected-(D6A-~{OUT0}-Pad41)") (class "Default")
      (node (ref "D6") (pin "41") (pinfunction "~{OUT0}_41") (pintype "output"))
    )
    (net (code "113") (name "unconnected-(D6A-~{OUT1}-Pad38)") (class "Default")
      (node (ref "D6") (pin "38") (pinfunction "~{OUT1}_38") (pintype "output"))
    )
    (net (code "114") (name "unconnected-(D6A-~{OUT2}-Pad20)") (class "Default")
      (node (ref "D6") (pin "20") (pinfunction "~{OUT2}_20") (pintype "output"))
    )
    (net (code "115") (name "unconnected-(D6A-~{OUT3}-Pad23)") (class "Default")
      (node (ref "D6") (pin "23") (pinfunction "~{OUT3}_23") (pintype "output"))
    )
    (net (code "116") (name "unconnected-(D6A-~{OUT5}(OUT5B)-Pad32)") (class "Default")
      (node (ref "D6") (pin "32") (pinfunction "~{OUT5}(OUT5B)_32") (pintype "output"))
    )
    (net (code "117") (name "unconnected-(D6A-~{OUT6}(OUT6B)-Pad27)") (class "Default")
      (node (ref "D6") (pin "27") (pinfunction "~{OUT6}(OUT6B)_27") (pintype "output"))
    )
    (net (code "118") (name "unconnected-(D6A-~{OUT7}(OUT7B)-Pad29)") (class "Default")
      (node (ref "D6") (pin "29") (pinfunction "~{OUT7}(OUT7B)_29") (pintype "output"))
    )
    (net (code "119") (name "unconnected-(D6A-~{PD}-Pad18)") (class "Default")
      (node (ref "D6") (pin "18") (pinfunction "~{PD}_18") (pintype "input"))
    )
    (net (code "120") (name "unconnected-(D6A-~{RESET}-Pad17)") (class "Default")
      (node (ref "D6") (pin "17") (pinfunction "~{RESET}_17") (pintype "input"))
    )
    (net (code "121") (name "unconnected-(D6A-~{SYNC}-Pad7)") (class "Default")
      (node (ref "D6") (pin "7") (pinfunction "~{SYNC}_7") (pintype "input"))
    )
    (net (code "122") (name "unconnected-(R43-Pad1)") (class "Default")
      (node (ref "R43") (pin "1") (pinfunction "1_1") (pintype "passive"))
    )
    (net (code "123") (name "unconnected-(T1-Pad5)") (class "Default")
      (node (ref "T1") (pin "5") (pinfunction "5_5") (pintype "passive"))
    )
    (net (code "124") (name "unconnected-(T2-Pad5)") (class "Default")
      (node (ref "T2") (pin "5") (pinfunction "5_5") (pintype "passive"))
    )
  )
)
